# PAPRika_PCB.net
KiCad netlist of a schematic drawn in Altium Designer
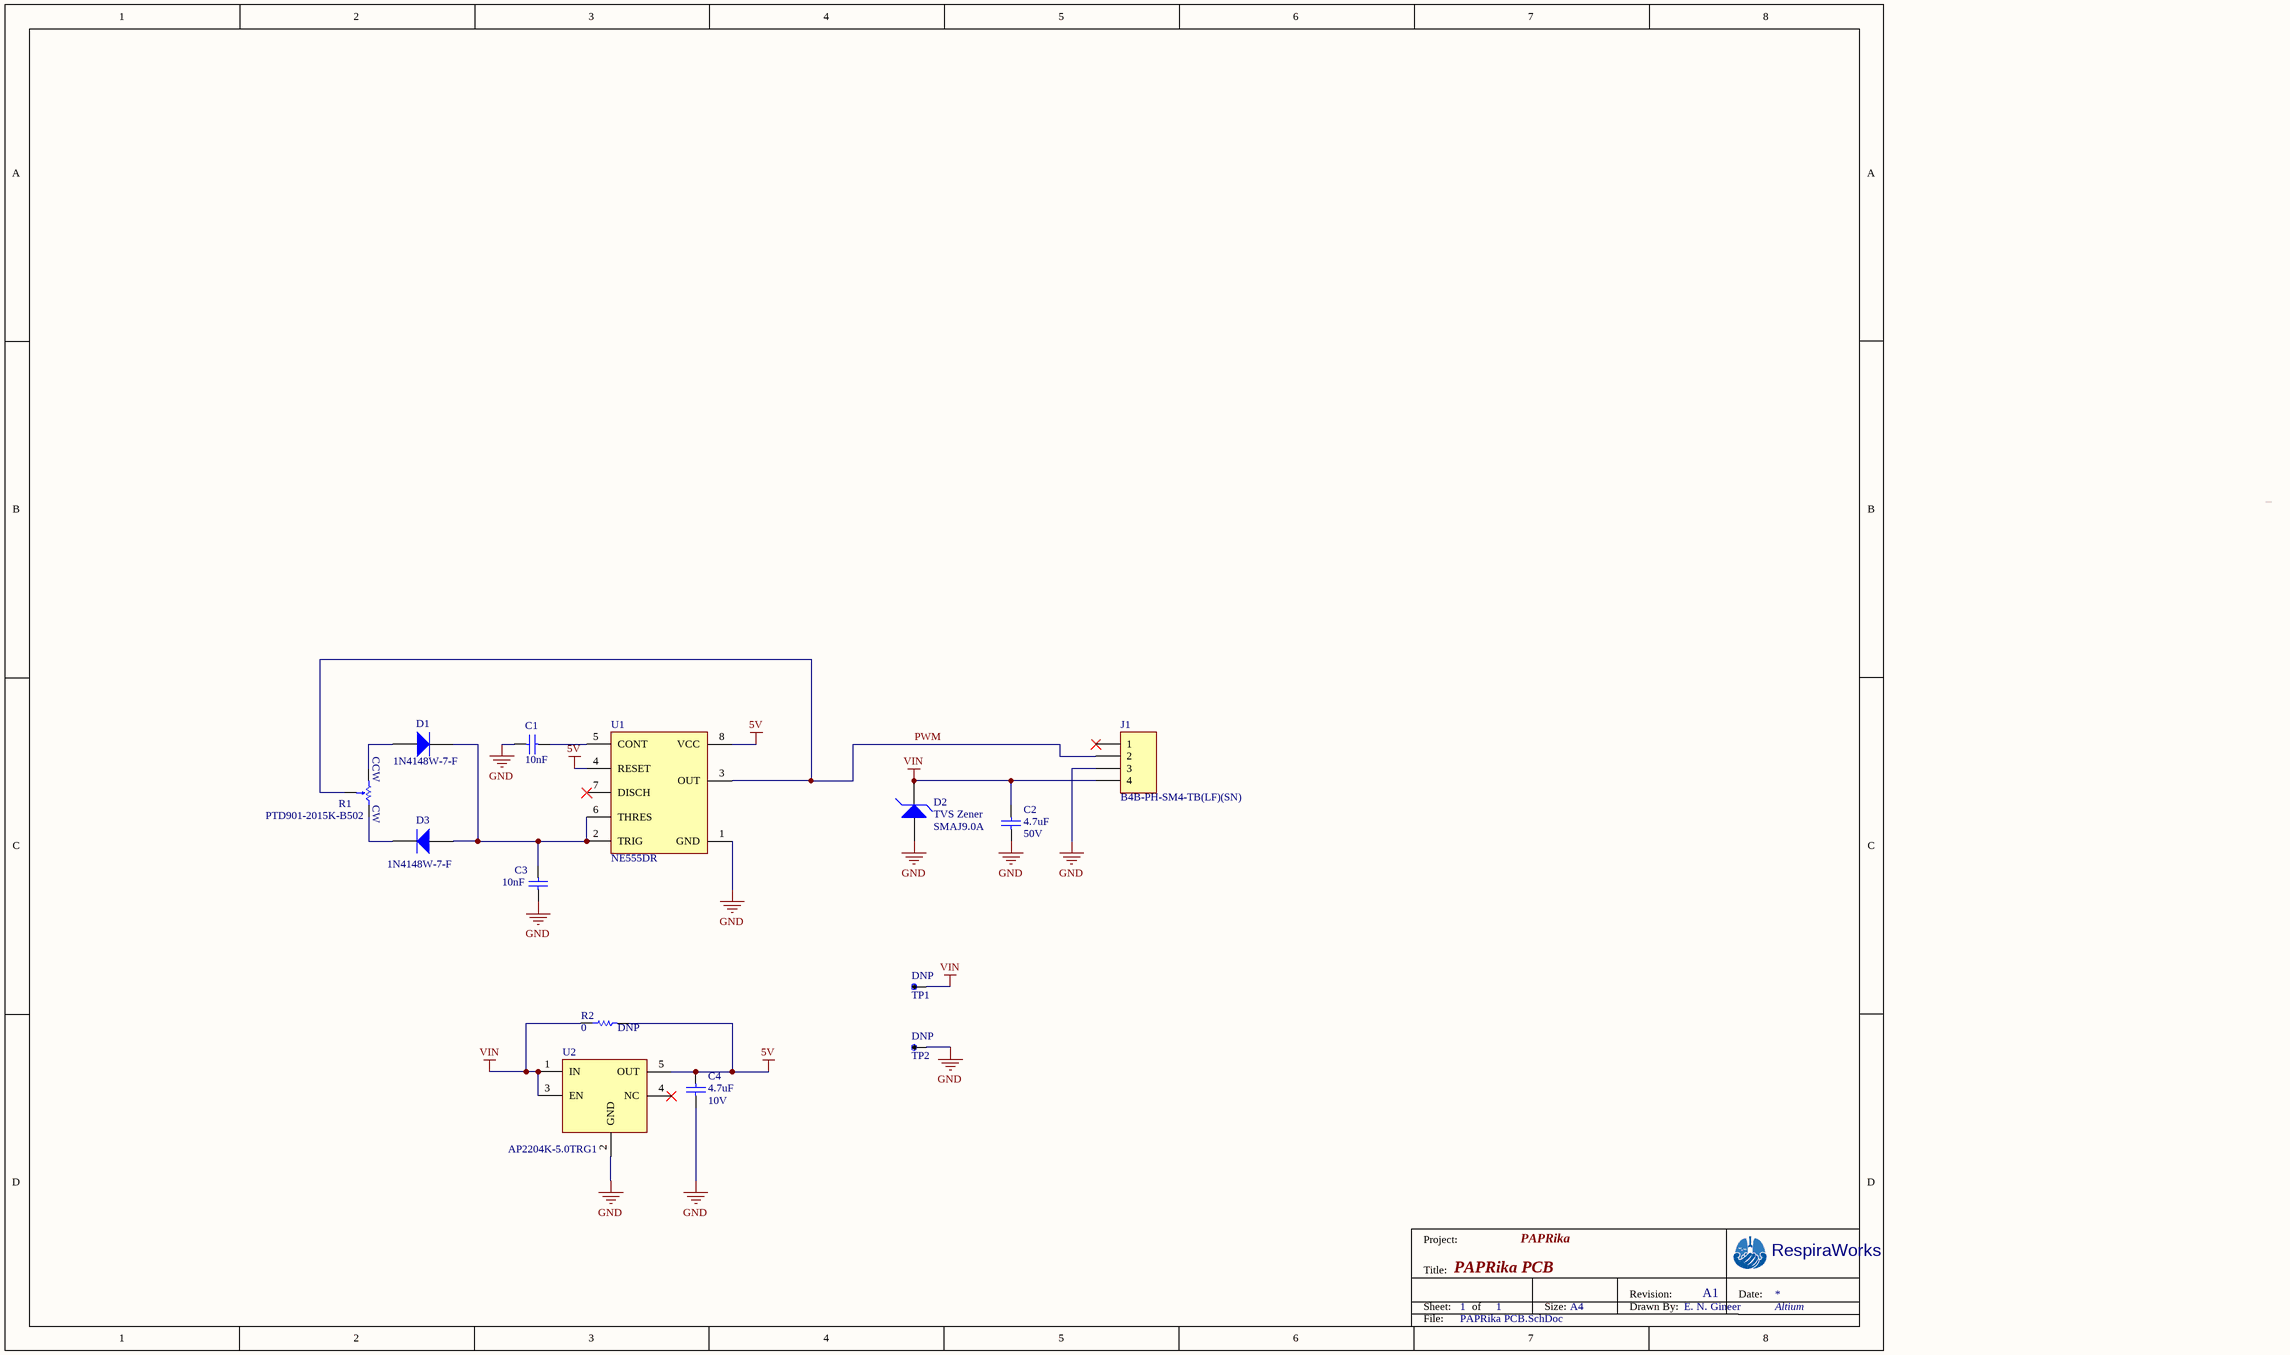
[diagram p0: PAPRika PCB.SchDoc]

(export (version "E")
  (design (tool "Eeschema 10.0.6"))
  (components
    (comp (ref "C1")
      (value "10nF")
      (footprint "CAP0603")
      (description "Cap 0603")
      (fields (field (name "MANUFACTURER") "Samsung") (field (name "Comment") "CAP 0603"))
      (libsource (lib "generic") (part "CAP 0603"))
    )
    (comp (ref "C2")
      (value "4.7uF")
      (footprint "CAP0805")
      (description "Cap 0805")
      (fields
        (field (name "MANUFACTURER") "Samsung")
        (field (name "VOLTAGE") "50V")
        (field (name "Comment") "CAP 0805")
      )
      (libsource (lib "generic") (part "CAP 0805"))
    )
    (comp (ref "C3")
      (value "10nF")
      (footprint "CAP0603")
      (description "Cap 0603")
      (fields (field (name "MANUFACTURER") "Samsung") (field (name "Comment") "CAP 0603"))
      (libsource (lib "generic") (part "CAP 0603"))
    )
    (comp (ref "C4")
      (value "4.7uF")
      (footprint "CAP0603")
      (description "Cap 0603")
      (fields
        (field (name "MANUFACTURER") "Samsung")
        (field (name "VOLTAGE") "10V")
        (field (name "Comment") "CAP 0603")
      )
      (libsource (lib "generic") (part "CAP 0603"))
    )
    (comp (ref "D1")
      (value "1N4148W-7-F")
      (footprint "SOD-123")
      (description "Ultra-Fast Signal Diode, Silicon, 100V, 300mA")
      (fields (field (name "MANUFACTURER") "Diodes Inc.") (field (name "MANUFACTURER P/N") "1N4148W-7-F"))
      (libsource (lib "diodes-inc") (part "1N4148W-7-F"))
    )
    (comp (ref "D2")
      (value "TVS Zener")
      (footprint "DO-214AC")
      (description "TVS DIODE 9V 15.4V DO214AC")
      (fields (field (name "MANUFACTURER") "Littelfuse") (field (name "MANUFACTURER P/N") "SMAJ9.0A"))
      (libsource (lib "littelfuse") (part "SMAJ9.0A"))
    )
    (comp (ref "D3")
      (value "1N4148W-7-F")
      (footprint "SOD-123")
      (description "Ultra-Fast Signal Diode, Silicon, 100V, 300mA")
      (fields (field (name "MANUFACTURER") "Diodes Inc.") (field (name "MANUFACTURER P/N") "1N4148W-7-F"))
      (libsource (lib "diodes-inc") (part "1N4148W-7-F"))
    )
    (comp (ref "J1")
      (value "B4B-PH-SM4-TB(LF)(SN)")
      (footprint "B4B-PH-SM4-TB")
      (description "JST 4-pin Male PCB Straight 2.00mm")
      (fields (field (name "MANUFACTURER") "JST") (field (name "MANUFACTURER P/N") "B4B-PH-SM4-TB(LF)(SN)"))
      (libsource (lib "JST") (part "B4B-PH-SM4-TB(LF)(SN)"))
    )
    (comp (ref "R1")
      (value "PTD901-2015K-B502")
      (footprint "PTD901")
      (description "POT 5K OHM 1/20W CARBON LINEAR")
      (fields (field (name "MANUFACTURER") "Bourns") (field (name "MANUFACTURER P/N") "PTD901-2015K-B502"))
      (libsource (lib "bourns") (part "PTD901-2015K-B502"))
    )
    (comp (ref "R2")
      (value "0")
      (footprint "RES0603")
      (description "Res 0603")
      (fields
        (field (name "MANUFACTURER") "Yageo")
        (field (name "DO NOT POPULATE") "DNP")
        (field (name "Comment") "RES 0603")
      )
      (libsource (lib "generic") (part "RES 0603"))
    )
    (comp (ref "TP1")
      (value "TP-5001-RED")
      (footprint "TP-5001-BLACK")
      (description "Keystone 5001 BLACK TH Mini Testpoint")
      (fields (field (name "MANUFACTURER") "Keystone") (field (name "DO NOT POPULATE") "DNP"))
      (libsource (lib "generic") (part "TP-5001-BLACK"))
    )
    (comp (ref "TP2")
      (value "TP-5001-RED")
      (footprint "TP-5001-BLACK")
      (description "Keystone 5001 BLACK TH Mini Testpoint")
      (fields (field (name "MANUFACTURER") "Keystone") (field (name "DO NOT POPULATE") "DNP"))
      (libsource (lib "generic") (part "TP-5001-BLACK"))
    )
    (comp (ref "U1")
      (value "NE555DR")
      (footprint "8-D")
      (description "IC OSC SGL TIMER 100KHZ 8-SOIC")
      (fields (field (name "MANUFACTURER") "Texas Instruments") (field (name "MANUFACTURER P/N") "NE555DR"))
      (libsource (lib "ti") (part "NE555DR"))
    )
    (comp (ref "U2")
      (value "AP2204K-5.0TRG1")
      (footprint "5-SOT23")
      (description "IC REG LINEAR 5V 150MA SOT23-5")
      (fields (field (name "MANUFACTURER") "Diodes Inc.") (field (name "MANUFACTURER P/N") "AP2204K-5.0TRG1"))
      (libsource (lib "diodes-inc") (part "AP2204K-5.0TRG1"))
    )
  )
  (nets
    (net (code "1") (name "/PWM") (class "Default")
      (node (ref "J1") (pin "2") (pinfunction "2_2") (pintype "passive"))
      (node (ref "R1") (pin "2") (pinfunction "2_2") (pintype "passive"))
      (node (ref "U1") (pin "3") (pinfunction "OUT_3") (pintype "passive"))
    )
    (net (code "2") (name "5V") (class "Default")
      (node (ref "C4") (pin "2") (pinfunction "2_2") (pintype "passive"))
      (node (ref "R2") (pin "2") (pinfunction "2_2") (pintype "passive"))
      (node (ref "U1") (pin "4") (pinfunction "RESET_4") (pintype "passive"))
      (node (ref "U1") (pin "8") (pinfunction "VCC_8") (pintype "passive"))
      (node (ref "U2") (pin "5") (pinfunction "OUT_5") (pintype "passive"))
    )
    (net (code "3") (name "GND") (class "Default")
      (node (ref "C1") (pin "2") (pinfunction "2_2") (pintype "passive"))
      (node (ref "C2") (pin "1") (pinfunction "1_1") (pintype "passive"))
      (node (ref "C3") (pin "1") (pinfunction "1_1") (pintype "passive"))
      (node (ref "C4") (pin "1") (pinfunction "1_1") (pintype "passive"))
      (node (ref "D2") (pin "A") (pinfunction "A_A") (pintype "passive"))
      (node (ref "J1") (pin "3") (pinfunction "3_3") (pintype "passive"))
      (node (ref "TP2") (pin "1") (pinfunction "1_1") (pintype "passive"))
      (node (ref "U1") (pin "1") (pinfunction "GND_1") (pintype "passive"))
      (node (ref "U2") (pin "2") (pinfunction "GND_2") (pintype "passive"))
    )
    (net (code "4") (name "Net-(D1-PadA)") (class "Default")
      (node (ref "D1") (pin "A") (pinfunction "A_A") (pintype "passive"))
      (node (ref "R1") (pin "1") (pinfunction "1_1") (pintype "passive"))
    )
    (net (code "5") (name "Net-(D3-PadK)") (class "Default")
      (node (ref "D3") (pin "K") (pinfunction "K_K") (pintype "passive"))
      (node (ref "R1") (pin "3") (pinfunction "3_3") (pintype "passive"))
    )
    (net (code "6") (name "Net-(U1-CONT)") (class "Default")
      (node (ref "C1") (pin "1") (pinfunction "1_1") (pintype "passive"))
      (node (ref "U1") (pin "5") (pinfunction "CONT_5") (pintype "passive"))
    )
    (net (code "7") (name "Net-(U1-THRES)") (class "Default")
      (node (ref "C3") (pin "2") (pinfunction "2_2") (pintype "passive"))
      (node (ref "D1") (pin "K") (pinfunction "K_K") (pintype "passive"))
      (node (ref "D3") (pin "A") (pinfunction "A_A") (pintype "passive"))
      (node (ref "U1") (pin "2") (pinfunction "TRIG_2") (pintype "passive"))
      (node (ref "U1") (pin "6") (pinfunction "THRES_6") (pintype "passive"))
    )
    (net (code "8") (name "VIN") (class "Default")
      (node (ref "C2") (pin "2") (pinfunction "2_2") (pintype "passive"))
      (node (ref "D2") (pin "K") (pinfunction "K_K") (pintype "passive"))
      (node (ref "J1") (pin "4") (pinfunction "4_4") (pintype "passive"))
      (node (ref "R2") (pin "1") (pinfunction "1_1") (pintype "passive"))
      (node (ref "TP1") (pin "1") (pinfunction "1_1") (pintype "passive"))
      (node (ref "U2") (pin "1") (pinfunction "IN_1") (pintype "passive"))
      (node (ref "U2") (pin "3") (pinfunction "EN_3") (pintype "passive"))
    )
    (net (code "9") (name "unconnected-(J1-Pad1)") (class "Default")
      (node (ref "J1") (pin "1") (pinfunction "1_1") (pintype "passive+no_connect"))
    )
    (net (code "10") (name "unconnected-(U1-DISCH-Pad7)") (class "Default")
      (node (ref "U1") (pin "7") (pinfunction "DISCH_7") (pintype "passive+no_connect"))
    )
    (net (code "11") (name "unconnected-(U2-NC-Pad4)") (class "Default")
      (node (ref "U2") (pin "4") (pinfunction "NC_4") (pintype "passive+no_connect"))
    )
  )
)
